# vemt.net
KiCad netlist of a schematic drawn in Altium Designer
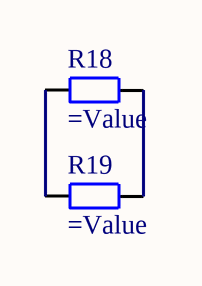
[diagram p0: vemt.SchDoc]

(export (version "E")
  (design (tool "Eeschema 10.0.6"))
  (components
    (comp (ref "R18")
      (value "~")
      (footprint "res0805")
      (libsource (lib "AlexChistiakov") (part "Resistor SMD"))
    )
    (comp (ref "R19")
      (value "~")
      (footprint "smd2010")
      (libsource (lib "AlexChistiakov") (part "Resistor SMD"))
    )
  )
  (nets
    (net (code "1") (name "Net-(R18-Pad1)") (class "Default")
      (node (ref "R18") (pin "1") (pinfunction "1_1") (pintype "passive"))
      (node (ref "R19") (pin "1") (pinfunction "1_1") (pintype "passive"))
    )
    (net (code "2") (name "Net-(R18-Pad2)") (class "Default")
      (node (ref "R18") (pin "2") (pinfunction "2_2") (pintype "passive"))
      (node (ref "R19") (pin "2") (pinfunction "2_2") (pintype "passive"))
    )
  )
)
